# Generator.net
KiCad netlist of a schematic drawn in Altium Designer
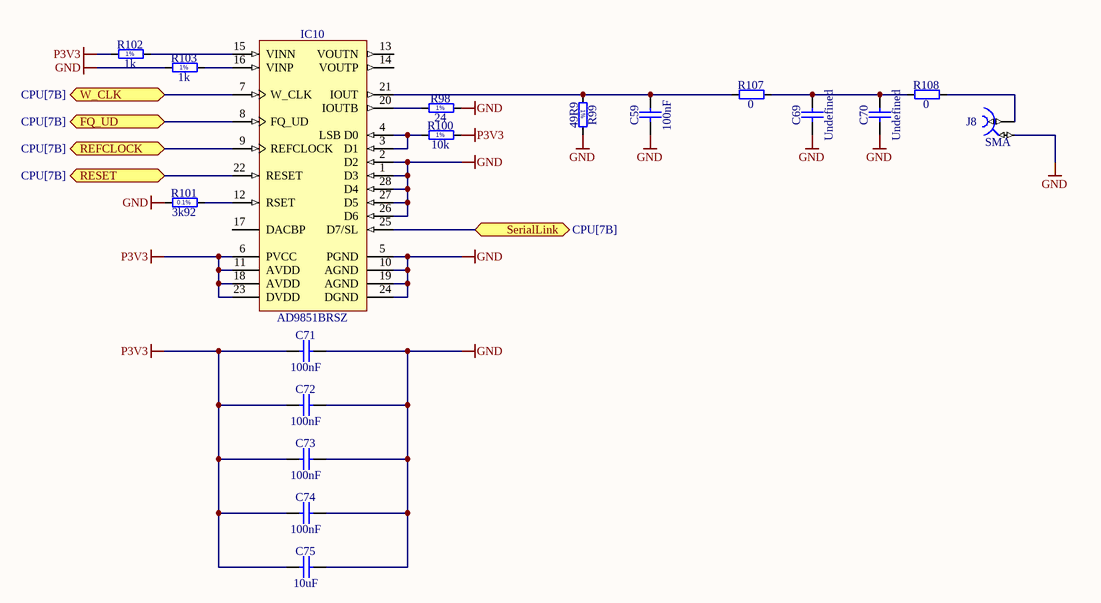
[diagram p0: Generator.SchDoc]

(export (version "E")
  (design (tool "Eeschema 10.0.6"))
  (components
    (comp (ref "C59")
      (value "100nF")
      (footprint "CAPC0603X33N")
      (description "Non-polarised capacitor")
      (fields
        (field (name "PART NUMBER") "CC0201_100NF_6.3V_10%_X5R")
        (field (name "VOLTAGE") "6.3V")
        (field (name "AUTHOR") "CERN DEM JLC")
      )
      (libsource (lib "Capacitors") (part "Capacitor - non polarized"))
    )
    (comp (ref "C69")
      (value "Undefined")
      (footprint "CAPC1608X90N")
      (description "Non-polarised capacitor")
      (fields (field (name "PART NUMBER") "CC0603_NO-VALUE") (field (name "AUTHOR") "CERN DEM MR"))
      (libsource (lib "Capacitors") (part "Capacitor - non polarized"))
    )
    (comp (ref "C70")
      (value "Undefined")
      (footprint "CAPC1608X90N")
      (description "Non-polarised capacitor")
      (fields (field (name "PART NUMBER") "CC0603_NO-VALUE") (field (name "AUTHOR") "CERN DEM MR"))
      (libsource (lib "Capacitors") (part "Capacitor - non polarized"))
    )
    (comp (ref "C71")
      (value "100nF")
      (footprint "CAPC0603X33N")
      (description "Non-polarised capacitor")
      (fields
        (field (name "PART NUMBER") "CC0201_100NF_6.3V_10%_X5R")
        (field (name "VOLTAGE") "6.3V")
        (field (name "AUTHOR") "CERN DEM JLC")
      )
      (libsource (lib "Capacitors") (part "Capacitor - non polarized"))
    )
    (comp (ref "C72")
      (value "100nF")
      (footprint "CAPC0603X33N")
      (description "Non-polarised capacitor")
      (fields
        (field (name "PART NUMBER") "CC0201_100NF_6.3V_10%_X5R")
        (field (name "VOLTAGE") "6.3V")
        (field (name "AUTHOR") "CERN DEM JLC")
      )
      (libsource (lib "Capacitors") (part "Capacitor - non polarized"))
    )
    (comp (ref "C73")
      (value "100nF")
      (footprint "CAPC0603X33N")
      (description "Non-polarised capacitor")
      (fields
        (field (name "PART NUMBER") "CC0201_100NF_6.3V_10%_X5R")
        (field (name "VOLTAGE") "6.3V")
        (field (name "AUTHOR") "CERN DEM JLC")
      )
      (libsource (lib "Capacitors") (part "Capacitor - non polarized"))
    )
    (comp (ref "C74")
      (value "100nF")
      (footprint "CAPC0603X33N")
      (description "Non-polarised capacitor")
      (fields
        (field (name "PART NUMBER") "CC0201_100NF_6.3V_10%_X5R")
        (field (name "VOLTAGE") "6.3V")
        (field (name "AUTHOR") "CERN DEM JLC")
      )
      (libsource (lib "Capacitors") (part "Capacitor - non polarized"))
    )
    (comp (ref "C75")
      (value "10uF")
      (footprint "CAPC1608X80N")
      (description "Non-polarised capacitor")
      (fields
        (field (name "PART NUMBER") "CC0603_10UF_10V_10%_X5R")
        (field (name "VOLTAGE") "10V")
        (field (name "AUTHOR") "CERN DEM JLC")
      )
      (libsource (lib "Capacitors") (part "Capacitor - non polarized"))
    )
    (comp (ref "IC10")
      (value "AD9851BRSZ")
      (footprint "SOP65P780X200-28N")
      (description "CMOS 180MHz DDS/DAC Synthesizer")
      (fields (field (name "MANUFACTURER") "ANALOG DEVICES") (field (name "AUTHOR") "CERN DEM JMW"))
      (libsource (lib "ICs And Semiconductors") (part "AD9851BRSZ"))
    )
    (comp (ref "J8")
      (value "SMA")
      (footprint "HUBER-SUHNER_85_SMA-50-0-101/111_NE")
      (fields
        (field (name "PART NUMBER") "HUBER-SUHNER_85_SMA-50-0-101/111_NE")
        (field (name "MANUFACTURER") "HUBER+SUHNER")
        (field (name "MANUFACTURER PART NUMBER") "85_SMA-50-0-101/111_NE")
        (field (name "AUTHOR") "CERN DEM JLC")
      )
      (libsource (lib "Connectors") (part "Coax_1Female_1Shield"))
    )
    (comp (ref "R98")
      (value "24")
      (footprint "RESC1005X40N")
      (description "Resistor - 1%")
      (fields
        (field (name "PART NUMBER") "R0402_24R_1%_0.0625W_100PPM")
        (field (name "POWER") "0.0625W")
        (field (name "AUTHOR") "CERN DEM JLC")
      )
      (libsource (lib "Resistors") (part "Resistor - 1%"))
    )
    (comp (ref "R99")
      (value "49R9")
      (footprint "RESC1005X40N")
      (description "Resistor - 1%")
      (fields
        (field (name "PART NUMBER") "R0402_49R9_1%_0.0625W_100PPM")
        (field (name "POWER") "0.0625W")
        (field (name "AUTHOR") "CERN DEM JLC")
      )
      (libsource (lib "Resistors") (part "Resistor - 1%"))
    )
    (comp (ref "R100")
      (value "10k")
      (footprint "RESC1005X40N")
      (description "Resistor - 1%")
      (fields
        (field (name "PART NUMBER") "R0402_10K_1%_0.0625W_100PPM")
        (field (name "POWER") "0.0625W")
        (field (name "AUTHOR") "CERN DEM JLC")
      )
      (libsource (lib "Resistors") (part "Resistor - 1%"))
    )
    (comp (ref "R101")
      (value "3k92")
      (footprint "RESC1608X55N")
      (description "Resistor - 0.1%")
      (fields
        (field (name "PART NUMBER") "R0603_3K92_0.1%_0.063W_10PPM")
        (field (name "POWER") "0.063W")
        (field (name "AUTHOR") "CERN DEM JLC")
      )
      (libsource (lib "Resistors") (part "Resistor - 0.1%"))
    )
    (comp (ref "R102")
      (value "1k")
      (footprint "RESC1005X40N")
      (description "Resistor - 1%")
      (fields
        (field (name "PART NUMBER") "R0402_1K_1%_0.0625W_100PPM")
        (field (name "POWER") "0.0625W")
        (field (name "AUTHOR") "CERN DEM JLC")
      )
      (libsource (lib "Resistors") (part "Resistor - 1%"))
    )
    (comp (ref "R103")
      (value "1k")
      (footprint "RESC1005X40N")
      (description "Resistor - 1%")
      (fields
        (field (name "PART NUMBER") "R0402_1K_1%_0.0625W_100PPM")
        (field (name "POWER") "0.0625W")
        (field (name "AUTHOR") "CERN DEM JLC")
      )
      (libsource (lib "Resistors") (part "Resistor - 1%"))
    )
    (comp (ref "R107")
      (value "0")
      (footprint "RESC1608X55N")
      (description "Resistor")
      (fields
        (field (name "PART NUMBER") "R0603_0R_JUMPER")
        (field (name "MANUFACTURER") "GENERIC")
        (field (name "AUTHOR") "CERN DEM JLC")
      )
      (libsource (lib "Resistors") (part "Resistor"))
    )
    (comp (ref "R108")
      (value "0")
      (footprint "RESC1608X55N")
      (description "Resistor")
      (fields
        (field (name "PART NUMBER") "R0603_0R_JUMPER")
        (field (name "MANUFACTURER") "GENERIC")
        (field (name "AUTHOR") "CERN DEM JLC")
      )
      (libsource (lib "Resistors") (part "Resistor"))
    )
  )
  (nets
    (net (code "1") (name "/FQ_UD") (class "Default")
      (node (ref "IC10") (pin "8") (pinfunction "FQ_UD_8") (pintype "input"))
    )
    (net (code "2") (name "/REFCLOCK") (class "Default")
      (node (ref "IC10") (pin "9") (pinfunction "REFCLOCK_9") (pintype "input"))
    )
    (net (code "3") (name "/RESET") (class "Default")
      (node (ref "IC10") (pin "22") (pinfunction "RESET_22") (pintype "input"))
    )
    (net (code "4") (name "/SerialLink") (class "Default")
      (node (ref "IC10") (pin "25") (pinfunction "D7/SL_25") (pintype "input"))
    )
    (net (code "5") (name "/W_CLK") (class "Default")
      (node (ref "IC10") (pin "7") (pinfunction "W_CLK_7") (pintype "input"))
    )
    (net (code "6") (name "GND") (class "Default")
      (node (ref "C59") (pin "1") (pinfunction "1_1") (pintype "passive"))
      (node (ref "C69") (pin "1") (pinfunction "1_1") (pintype "passive"))
      (node (ref "C70") (pin "1") (pinfunction "1_1") (pintype "passive"))
      (node (ref "C71") (pin "2") (pinfunction "2_2") (pintype "passive"))
      (node (ref "C72") (pin "2") (pinfunction "2_2") (pintype "passive"))
      (node (ref "C73") (pin "2") (pinfunction "2_2") (pintype "passive"))
      (node (ref "C74") (pin "2") (pinfunction "2_2") (pintype "passive"))
      (node (ref "C75") (pin "2") (pinfunction "2_2") (pintype "passive"))
      (node (ref "IC10") (pin "1") (pinfunction "D3_1") (pintype "input"))
      (node (ref "IC10") (pin "10") (pinfunction "AGND_10") (pintype "power_in"))
      (node (ref "IC10") (pin "19") (pinfunction "AGND_19") (pintype "power_in"))
      (node (ref "IC10") (pin "2") (pinfunction "D2_2") (pintype "input"))
      (node (ref "IC10") (pin "24") (pinfunction "DGND_24") (pintype "power_in"))
      (node (ref "IC10") (pin "26") (pinfunction "D6_26") (pintype "input"))
      (node (ref "IC10") (pin "27") (pinfunction "D5_27") (pintype "input"))
      (node (ref "IC10") (pin "28") (pinfunction "D4_28") (pintype "input"))
      (node (ref "IC10") (pin "5") (pinfunction "PGND_5") (pintype "power_in"))
      (node (ref "J8") (pin "2") (pinfunction "2_2") (pintype "bidirectional"))
      (node (ref "R101") (pin "1") (pinfunction "1_1") (pintype "passive"))
      (node (ref "R103") (pin "1") (pinfunction "1_1") (pintype "passive"))
      (node (ref "R98") (pin "2") (pinfunction "2_2") (pintype "passive"))
      (node (ref "R99") (pin "2") (pinfunction "2_2") (pintype "passive"))
    )
    (net (code "7") (name "Net-(C69-Pad2)") (class "Default")
      (node (ref "C69") (pin "2") (pinfunction "2_2") (pintype "passive"))
      (node (ref "C70") (pin "2") (pinfunction "2_2") (pintype "passive"))
      (node (ref "R107") (pin "2") (pinfunction "2_2") (pintype "passive"))
      (node (ref "R108") (pin "1") (pinfunction "1_1") (pintype "passive"))
    )
    (net (code "8") (name "Net-(IC10-D1)") (class "Default")
      (node (ref "IC10") (pin "3") (pinfunction "D1_3") (pintype "input"))
      (node (ref "IC10") (pin "4") (pinfunction "LSB_D0_4") (pintype "input"))
      (node (ref "R100") (pin "1") (pinfunction "1_1") (pintype "passive"))
    )
    (net (code "9") (name "Net-(IC10-IOUT)") (class "Default")
      (node (ref "C59") (pin "2") (pinfunction "2_2") (pintype "passive"))
      (node (ref "IC10") (pin "21") (pinfunction "IOUT_21") (pintype "output"))
      (node (ref "R107") (pin "1") (pinfunction "1_1") (pintype "passive"))
      (node (ref "R99") (pin "1") (pinfunction "1_1") (pintype "passive"))
    )
    (net (code "10") (name "Net-(IC10-IOUTB)") (class "Default")
      (node (ref "IC10") (pin "20") (pinfunction "IOUTB_20") (pintype "output"))
      (node (ref "R98") (pin "1") (pinfunction "1_1") (pintype "passive"))
    )
    (net (code "11") (name "Net-(IC10-RSET)") (class "Default")
      (node (ref "IC10") (pin "12") (pinfunction "RSET_12") (pintype "input"))
      (node (ref "R101") (pin "2") (pinfunction "2_2") (pintype "passive"))
    )
    (net (code "12") (name "Net-(IC10-VINN)") (class "Default")
      (node (ref "IC10") (pin "15") (pinfunction "VINN_15") (pintype "input"))
      (node (ref "R102") (pin "2") (pinfunction "2_2") (pintype "passive"))
    )
    (net (code "13") (name "Net-(IC10-VINP)") (class "Default")
      (node (ref "IC10") (pin "16") (pinfunction "VINP_16") (pintype "input"))
      (node (ref "R103") (pin "2") (pinfunction "2_2") (pintype "passive"))
    )
    (net (code "14") (name "Net-(J8-Pad1)") (class "Default")
      (node (ref "J8") (pin "1") (pinfunction "1_1") (pintype "bidirectional"))
      (node (ref "R108") (pin "2") (pinfunction "2_2") (pintype "passive"))
    )
    (net (code "15") (name "P3V3") (class "Default")
      (node (ref "C71") (pin "1") (pinfunction "1_1") (pintype "passive"))
      (node (ref "C72") (pin "1") (pinfunction "1_1") (pintype "passive"))
      (node (ref "C73") (pin "1") (pinfunction "1_1") (pintype "passive"))
      (node (ref "C74") (pin "1") (pinfunction "1_1") (pintype "passive"))
      (node (ref "C75") (pin "1") (pinfunction "1_1") (pintype "passive"))
      (node (ref "IC10") (pin "11") (pinfunction "AVDD_11") (pintype "power_in"))
      (node (ref "IC10") (pin "18") (pinfunction "AVDD_18") (pintype "power_in"))
      (node (ref "IC10") (pin "23") (pinfunction "DVDD_23") (pintype "power_in"))
      (node (ref "IC10") (pin "6") (pinfunction "PVCC_6") (pintype "power_in"))
      (node (ref "R100") (pin "2") (pinfunction "2_2") (pintype "passive"))
      (node (ref "R102") (pin "1") (pinfunction "1_1") (pintype "passive"))
    )
    (net (code "16") (name "unconnected-(IC10-DACBP-Pad17)") (class "Default")
      (node (ref "IC10") (pin "17") (pinfunction "DACBP_17") (pintype "passive"))
    )
    (net (code "17") (name "unconnected-(IC10-VOUTN-Pad13)") (class "Default")
      (node (ref "IC10") (pin "13") (pinfunction "VOUTN_13") (pintype "output"))
    )
    (net (code "18") (name "unconnected-(IC10-VOUTP-Pad14)") (class "Default")
      (node (ref "IC10") (pin "14") (pinfunction "VOUTP_14") (pintype "output"))
    )
  )
)
